# 2out_16A_bi_TS_V0_3.net
KiCad netlist of a schematic drawn in EAGLE
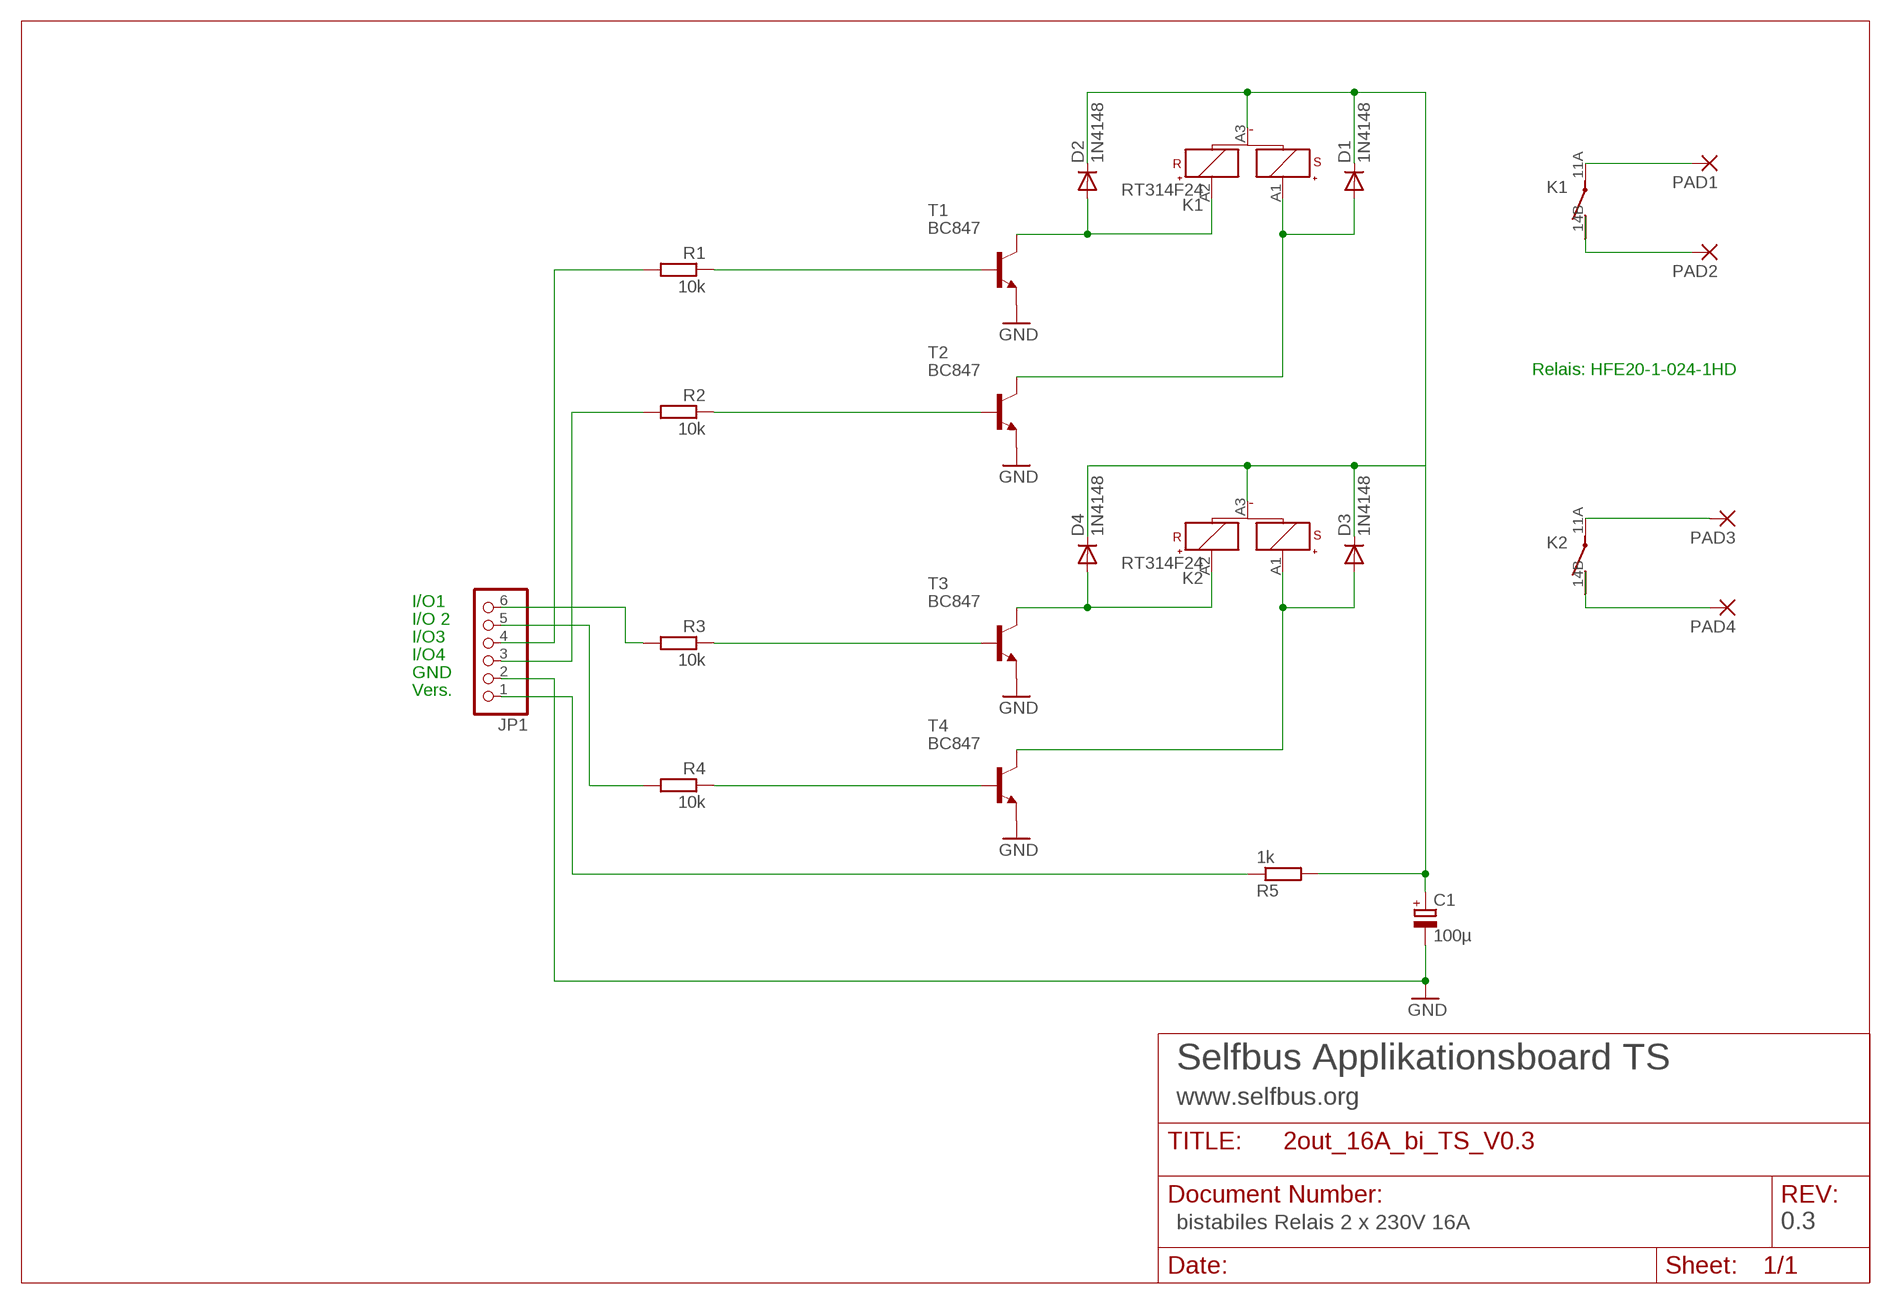
[diagram p0: schematic, sheet 1]

(export (version "E")
  (design (tool "Eeschema 10.0.6"))
  (components
    (comp (ref "C1")
      (value "100µ")
      (footprint "eagle-import:E3,5-8")
      (libsource (lib "eagle-import") (part "CPOL-EUE3.5-8"))
    )
    (comp (ref "D1")
      (value "1N4148")
      (footprint "eagle-import:MINIMELF")
      (libsource (lib "eagle-import") (part "DIODE-MINIMELF"))
    )
    (comp (ref "D2")
      (value "1N4148")
      (footprint "eagle-import:MINIMELF")
      (libsource (lib "eagle-import") (part "DIODE-MINIMELF"))
    )
    (comp (ref "D3")
      (value "1N4148")
      (footprint "eagle-import:MINIMELF")
      (libsource (lib "eagle-import") (part "DIODE-MINIMELF"))
    )
    (comp (ref "D4")
      (value "1N4148")
      (footprint "eagle-import:MINIMELF")
      (libsource (lib "eagle-import") (part "DIODE-MINIMELF"))
    )
    (comp (ref "JP1")
      (value "PINHD-1X6/90")
      (footprint "eagle-import:1X06_90")
      (libsource (lib "eagle-import") (part "PINHD-1X6/90"))
    )
    (comp (ref "K1")
      (value "RT314F24")
      (footprint "eagle-import:RT1-BI")
      (libsource (lib "eagle-import") (part "RT?F31424"))
    )
    (comp (ref "K2")
      (value "RT314F24")
      (footprint "eagle-import:RT1-BI")
      (libsource (lib "eagle-import") (part "RT?F31424"))
    )
    (comp (ref "PAD1")
      (value "3,81/1,4")
      (footprint "eagle-import:3,81_1,4")
      (libsource (lib "eagle-import") (part "3,81/1,4"))
    )
    (comp (ref "PAD2")
      (value "3,81/1,4")
      (footprint "eagle-import:3,81_1,4")
      (libsource (lib "eagle-import") (part "3,81/1,4"))
    )
    (comp (ref "PAD3")
      (value "3,81/1,4")
      (footprint "eagle-import:3,81_1,4")
      (libsource (lib "eagle-import") (part "3,81/1,4"))
    )
    (comp (ref "PAD4")
      (value "3,81/1,4")
      (footprint "eagle-import:3,81_1,4")
      (libsource (lib "eagle-import") (part "3,81/1,4"))
    )
    (comp (ref "R1")
      (value "10k")
      (footprint "eagle-import:M1206")
      (libsource (lib "eagle-import") (part "R-EU_M1206"))
    )
    (comp (ref "R2")
      (value "10k")
      (footprint "eagle-import:M1206")
      (libsource (lib "eagle-import") (part "R-EU_M1206"))
    )
    (comp (ref "R3")
      (value "10k")
      (footprint "eagle-import:M1206")
      (libsource (lib "eagle-import") (part "R-EU_M1206"))
    )
    (comp (ref "R4")
      (value "10k")
      (footprint "eagle-import:M1206")
      (libsource (lib "eagle-import") (part "R-EU_M1206"))
    )
    (comp (ref "R5")
      (value "1k")
      (footprint "eagle-import:M1206")
      (libsource (lib "eagle-import") (part "R-EU_M1206"))
    )
    (comp (ref "T1")
      (value "BC847")
      (footprint "eagle-import:SOT23")
      (libsource (lib "eagle-import") (part "BC847"))
    )
    (comp (ref "T2")
      (value "BC847")
      (footprint "eagle-import:SOT23")
      (libsource (lib "eagle-import") (part "BC847"))
    )
    (comp (ref "T3")
      (value "BC847")
      (footprint "eagle-import:SOT23")
      (libsource (lib "eagle-import") (part "BC847"))
    )
    (comp (ref "T4")
      (value "BC847")
      (footprint "eagle-import:SOT23")
      (libsource (lib "eagle-import") (part "BC847"))
    )
  )
  (nets
    (net (code "1") (name "GND") (class "Default")
      (node (ref "C1") (pin "-") (pinfunction "-_-") (pintype "passive"))
      (node (ref "JP1") (pin "2") (pinfunction "2_2") (pintype "passive"))
      (node (ref "T1") (pin "2") (pinfunction "E_2") (pintype "passive"))
      (node (ref "T2") (pin "2") (pinfunction "E_2") (pintype "passive"))
      (node (ref "T3") (pin "2") (pinfunction "E_2") (pintype "passive"))
      (node (ref "T4") (pin "2") (pinfunction "E_2") (pintype "passive"))
    )
    (net (code "2") (name "Net-(JP1-Pad1)") (class "Default")
      (node (ref "JP1") (pin "1") (pinfunction "1_1") (pintype "passive"))
      (node (ref "R5") (pin "1") (pinfunction "1_1") (pintype "passive"))
    )
    (net (code "3") (name "Net-(JP1-Pad3)") (class "Default")
      (node (ref "JP1") (pin "3") (pinfunction "3_3") (pintype "passive"))
      (node (ref "R2") (pin "2") (pinfunction "2_2") (pintype "passive"))
    )
    (net (code "4") (name "Net-(JP1-Pad4)") (class "Default")
      (node (ref "JP1") (pin "4") (pinfunction "4_4") (pintype "passive"))
      (node (ref "R1") (pin "2") (pinfunction "2_2") (pintype "passive"))
    )
    (net (code "5") (name "Net-(JP1-Pad5)") (class "Default")
      (node (ref "JP1") (pin "5") (pinfunction "5_5") (pintype "passive"))
      (node (ref "R4") (pin "2") (pinfunction "2_2") (pintype "passive"))
    )
    (net (code "6") (name "Net-(JP1-Pad6)") (class "Default")
      (node (ref "JP1") (pin "6") (pinfunction "6_6") (pintype "passive"))
      (node (ref "R3") (pin "2") (pinfunction "2_2") (pintype "passive"))
    )
    (net (code "7") (name "Net-(K1A--)") (class "Default")
      (node (ref "C1") (pin "+") (pinfunction "+_+") (pintype "passive"))
      (node (ref "D1") (pin "C") (pinfunction "C_C") (pintype "passive"))
      (node (ref "D2") (pin "C") (pinfunction "C_C") (pintype "passive"))
      (node (ref "D3") (pin "C") (pinfunction "C_C") (pintype "passive"))
      (node (ref "D4") (pin "C") (pinfunction "C_C") (pintype "passive"))
      (node (ref "K1") (pin "A3") (pinfunction "-_A3") (pintype "passive"))
      (node (ref "K2") (pin "A3") (pinfunction "-_A3") (pintype "passive"))
      (node (ref "R5") (pin "2") (pinfunction "2_2") (pintype "passive"))
    )
    (net (code "8") (name "Net-(K1A-R+)") (class "Default")
      (node (ref "D2") (pin "A") (pinfunction "A_A") (pintype "passive"))
      (node (ref "K1") (pin "A2") (pinfunction "R+_A2") (pintype "passive"))
      (node (ref "T1") (pin "3") (pinfunction "C_3") (pintype "passive"))
    )
    (net (code "9") (name "Net-(K1A-S+)") (class "Default")
      (node (ref "D1") (pin "A") (pinfunction "A_A") (pintype "passive"))
      (node (ref "K1") (pin "A1") (pinfunction "S+_A1") (pintype "passive"))
      (node (ref "T2") (pin "3") (pinfunction "C_3") (pintype "passive"))
    )
    (net (code "10") (name "Net-(K1B-PA)") (class "Default")
      (node (ref "K1") (pin "11A") (pinfunction "PA_11A") (pintype "passive"))
      (node (ref "PAD1") (pin "1") (pinfunction "P_1") (pintype "passive"))
    )
    (net (code "11") (name "Net-(K1B-SA)") (class "Default")
      (node (ref "K1") (pin "14B") (pinfunction "SA_14B") (pintype "passive"))
      (node (ref "PAD2") (pin "1") (pinfunction "P_1") (pintype "passive"))
    )
    (net (code "12") (name "Net-(K2A-R+)") (class "Default")
      (node (ref "D4") (pin "A") (pinfunction "A_A") (pintype "passive"))
      (node (ref "K2") (pin "A2") (pinfunction "R+_A2") (pintype "passive"))
      (node (ref "T3") (pin "3") (pinfunction "C_3") (pintype "passive"))
    )
    (net (code "13") (name "Net-(K2A-S+)") (class "Default")
      (node (ref "D3") (pin "A") (pinfunction "A_A") (pintype "passive"))
      (node (ref "K2") (pin "A1") (pinfunction "S+_A1") (pintype "passive"))
      (node (ref "T4") (pin "3") (pinfunction "C_3") (pintype "passive"))
    )
    (net (code "14") (name "Net-(K2B-PA)") (class "Default")
      (node (ref "K2") (pin "11A") (pinfunction "PA_11A") (pintype "passive"))
      (node (ref "PAD3") (pin "1") (pinfunction "P_1") (pintype "passive"))
    )
    (net (code "15") (name "Net-(K2B-SA)") (class "Default")
      (node (ref "K2") (pin "14B") (pinfunction "SA_14B") (pintype "passive"))
      (node (ref "PAD4") (pin "1") (pinfunction "P_1") (pintype "passive"))
    )
    (net (code "16") (name "Net-(T1-B)") (class "Default")
      (node (ref "R1") (pin "1") (pinfunction "1_1") (pintype "passive"))
      (node (ref "T1") (pin "1") (pinfunction "B_1") (pintype "passive"))
    )
    (net (code "17") (name "Net-(T2-B)") (class "Default")
      (node (ref "R2") (pin "1") (pinfunction "1_1") (pintype "passive"))
      (node (ref "T2") (pin "1") (pinfunction "B_1") (pintype "passive"))
    )
    (net (code "18") (name "Net-(T3-B)") (class "Default")
      (node (ref "R3") (pin "1") (pinfunction "1_1") (pintype "passive"))
      (node (ref "T3") (pin "1") (pinfunction "B_1") (pintype "passive"))
    )
    (net (code "19") (name "Net-(T4-B)") (class "Default")
      (node (ref "R4") (pin "1") (pinfunction "1_1") (pintype "passive"))
      (node (ref "T4") (pin "1") (pinfunction "B_1") (pintype "passive"))
    )
  )
)
